# Solenoid_14.net
KiCad netlist of a schematic drawn in EAGLE
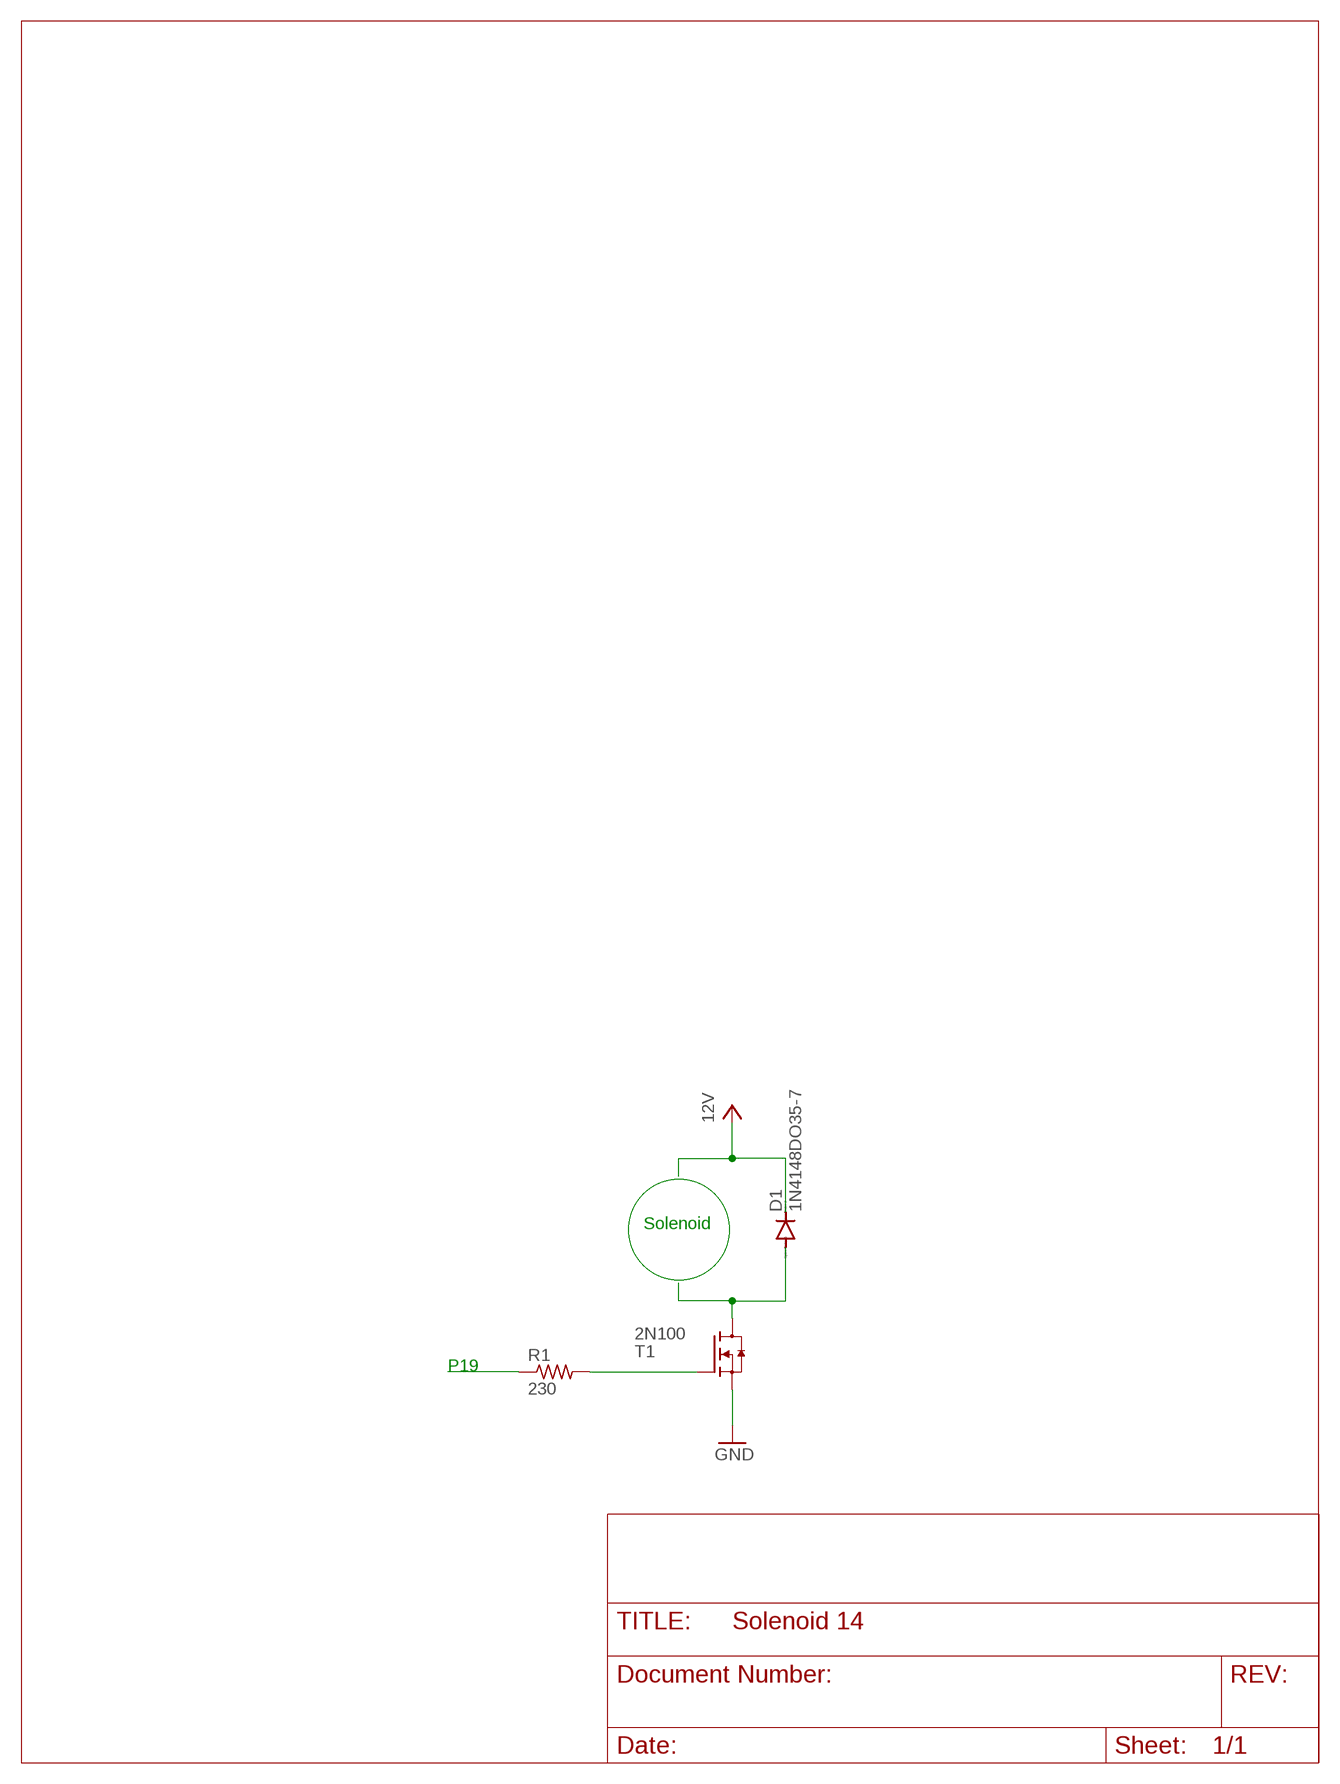
[diagram p0: schematic, sheet 1]

(export (version "E")
  (design (tool "Eeschema 10.0.6"))
  (components
    (comp (ref "D1")
      (value "1N4148DO35-7")
      (footprint "eagle-import:DO35-7")
      (libsource (lib "eagle-import") (part "1N4148DO35-7"))
    )
    (comp (ref "R1")
      (value "230")
      (footprint "eagle-import:0204_7")
      (libsource (lib "eagle-import") (part "R-US_0204/7"))
    )
    (comp (ref "T1")
      (value "2N100")
      (footprint "eagle-import:PG-TO263-7-3")
      (libsource (lib "eagle-import") (part "IPB180N06S4-H1"))
    )
  )
  (nets
    (net (code "1") (name "12V") (class "Default")
      (node (ref "D1") (pin "C") (pinfunction "C_C") (pintype "passive"))
    )
    (net (code "2") (name "GND") (class "Default")
      (node (ref "T1") (pin "2") (pinfunction "S_2") (pintype "passive"))
      (node (ref "T1") (pin "3") (pinfunction "S_3") (pintype "passive"))
      (node (ref "T1") (pin "5") (pinfunction "S_5") (pintype "passive"))
      (node (ref "T1") (pin "6") (pinfunction "S_6") (pintype "passive"))
      (node (ref "T1") (pin "7") (pinfunction "S_7") (pintype "passive"))
    )
    (net (code "3") (name "Net-(T1-D)") (class "Default")
      (node (ref "D1") (pin "A") (pinfunction "A_A") (pintype "passive"))
      (node (ref "T1") (pin "8") (pinfunction "D_8") (pintype "passive"))
    )
    (net (code "4") (name "Net-(T1-G)") (class "Default")
      (node (ref "R1") (pin "2") (pinfunction "2_2") (pintype "passive"))
      (node (ref "T1") (pin "1") (pinfunction "G_1") (pintype "passive"))
    )
    (net (code "5") (name "unconnected-(R1-Pad1)") (class "Default")
      (node (ref "R1") (pin "1") (pinfunction "1_1") (pintype "passive"))
    )
  )
)
